# Interface.net
KiCad netlist of a schematic drawn in Altium Designer
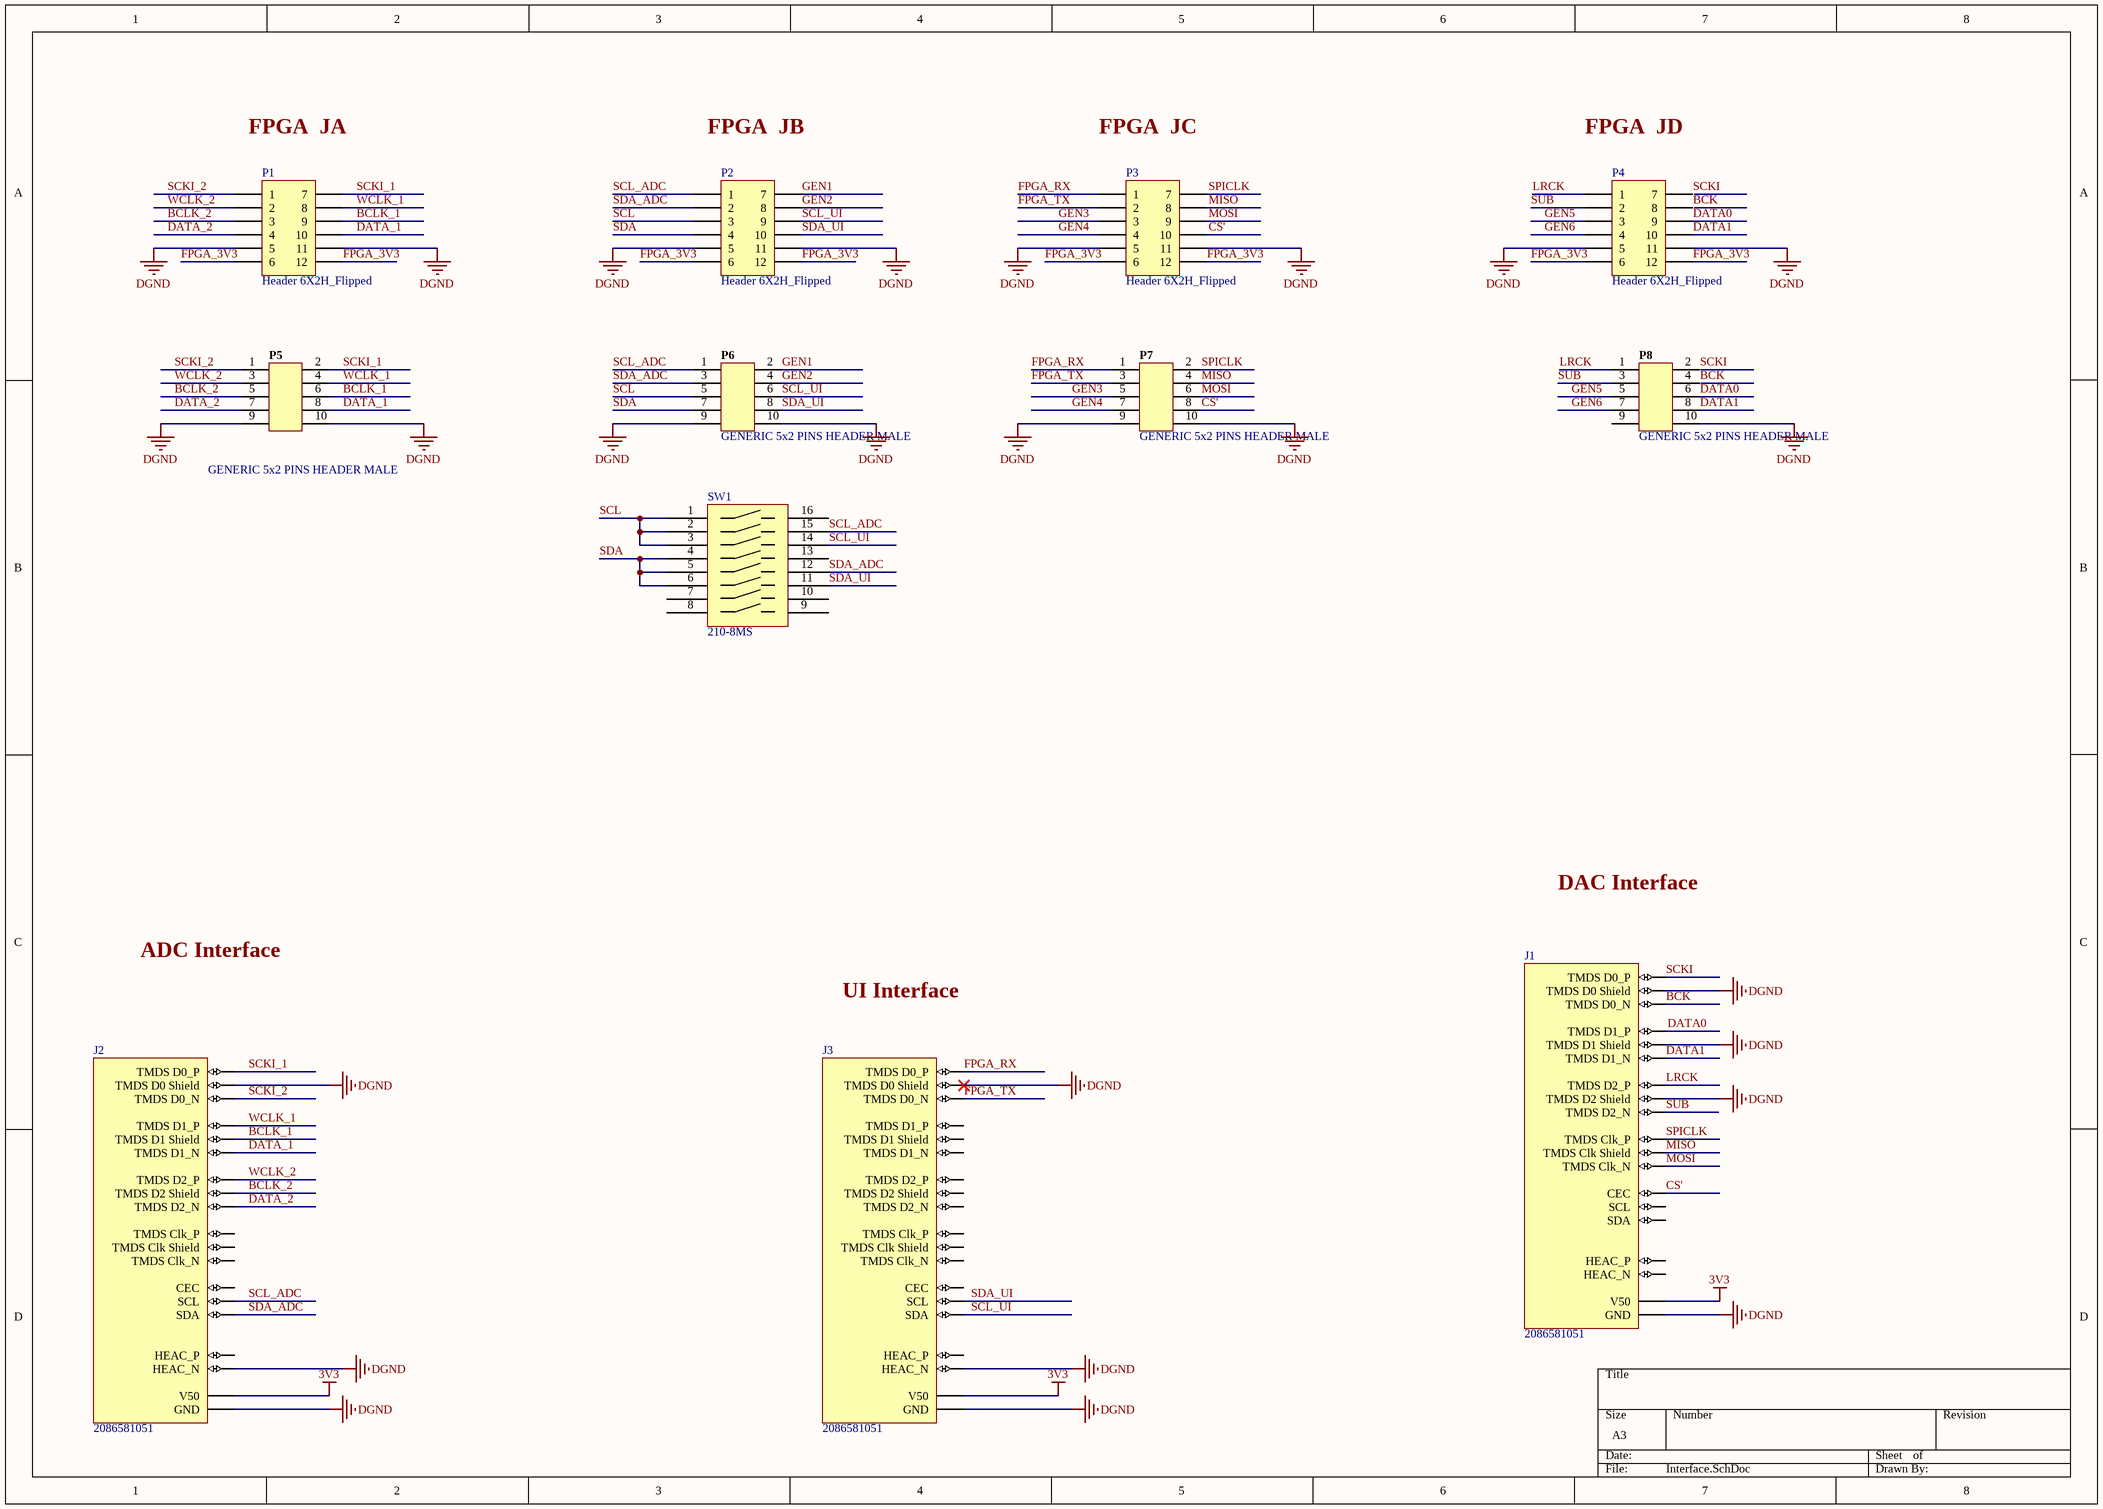
[diagram p0: Interface.SchDoc]

(export (version "E")
  (design (tool "Eeschema 10.0.6"))
  (components
    (comp (ref "J1")
      (value "2086581051")
      (footprint "2086581051")
      (description "CONN FEM SMD 19 90Deg HDMI")
      (fields (field (name "DESIGN ITEM ID") "2086581051") (field (name "MANUFACTURER") "Molex"))
      (libsource (lib "University of Malta - MEMENTO") (part "Symbol"))
    )
    (comp (ref "J2")
      (value "2086581051")
      (footprint "2086581051")
      (description "CONN FEM SMD 19 90Deg HDMI")
      (fields (field (name "DESIGN ITEM ID") "2086581051") (field (name "MANUFACTURER") "Molex"))
      (libsource (lib "University of Malta - MEMENTO") (part "Symbol"))
    )
    (comp (ref "J3")
      (value "2086581051")
      (footprint "2086581051")
      (description "CONN FEM SMD 19 90Deg HDMI")
      (fields (field (name "DESIGN ITEM ID") "2086581051") (field (name "MANUFACTURER") "Molex"))
      (libsource (lib "University of Malta - MEMENTO") (part "Symbol"))
    )
    (comp (ref "P1")
      (value "Header 6X2H_Flipped")
      (footprint "HDR2X6H_Flipped")
      (description "Header, 6-Pin, Dual row, Right Angle, Flipped")
      (fields (field (name "DESIGN ITEM ID") "Header 6X2H_Flipped"))
      (libsource (lib "University of Malta - MEMENTO") (part "Header 6X2H_Flipped"))
    )
    (comp (ref "P2")
      (value "Header 6X2H_Flipped")
      (footprint "HDR2X6H_Flipped")
      (description "Header, 6-Pin, Dual row, Right Angle, Flipped")
      (fields (field (name "DESIGN ITEM ID") "Header 6X2H_Flipped"))
      (libsource (lib "University of Malta - MEMENTO") (part "Header 6X2H_Flipped"))
    )
    (comp (ref "P3")
      (value "Header 6X2H_Flipped")
      (footprint "HDR2X6H_Flipped")
      (description "Header, 6-Pin, Dual row, Right Angle, Flipped")
      (fields (field (name "DESIGN ITEM ID") "Header 6X2H_Flipped"))
      (libsource (lib "University of Malta - MEMENTO") (part "Header 6X2H_Flipped"))
    )
    (comp (ref "P4")
      (value "Header 6X2H_Flipped")
      (footprint "HDR2X6H_Flipped")
      (description "Header, 6-Pin, Dual row, Right Angle, Flipped")
      (fields (field (name "DESIGN ITEM ID") "Header 6X2H_Flipped"))
      (libsource (lib "University of Malta - MEMENTO") (part "Header 6X2H_Flipped"))
    )
    (comp (ref "P5")
      (value "GENERIC 5x2 PINS HEADER MALE")
      (footprint "GENERIC 5PIN 2ROW HEADER 0")
      (description "CONN MAL TH 5x2 0Deg HEADER")
      (fields
        (field (name "DESIGN ITEM ID") "GENERIC 5x2 PINS HEADER MALE")
        (field (name "MANUFACTURER") "Generic")
      )
      (libsource (lib "University of Malta - MEMENTO") (part "GENERIC 5x2 PINS HEADER MALE"))
    )
    (comp (ref "P6")
      (value "GENERIC 5x2 PINS HEADER MALE")
      (footprint "GENERIC 5PIN 2ROW HEADER 0")
      (description "CONN MAL TH 5x2 0Deg HEADER")
      (fields
        (field (name "DESIGN ITEM ID") "GENERIC 5x2 PINS HEADER MALE")
        (field (name "MANUFACTURER") "Generic")
      )
      (libsource (lib "University of Malta - MEMENTO") (part "GENERIC 5x2 PINS HEADER MALE"))
    )
    (comp (ref "P7")
      (value "GENERIC 5x2 PINS HEADER MALE")
      (footprint "GENERIC 5PIN 2ROW HEADER 0")
      (description "CONN MAL TH 5x2 0Deg HEADER")
      (fields
        (field (name "DESIGN ITEM ID") "GENERIC 5x2 PINS HEADER MALE")
        (field (name "MANUFACTURER") "Generic")
      )
      (libsource (lib "University of Malta - MEMENTO") (part "GENERIC 5x2 PINS HEADER MALE"))
    )
    (comp (ref "P8")
      (value "GENERIC 5x2 PINS HEADER MALE")
      (footprint "GENERIC 5PIN 2ROW HEADER 0")
      (description "CONN MAL TH 5x2 0Deg HEADER")
      (fields
        (field (name "DESIGN ITEM ID") "GENERIC 5x2 PINS HEADER MALE")
        (field (name "MANUFACTURER") "Generic")
      )
      (libsource (lib "University of Malta - MEMENTO") (part "GENERIC 5x2 PINS HEADER MALE"))
    )
    (comp (ref "SW1")
      (value "210-8MS")
      (footprint "210-8MS")
      (description "SWITCH DIP SMD SPST 8 100mA 50V")
      (fields (field (name "MANUFACTURER") "C&K Components") (field (name "DESIGN ITEM ID") "210-8MS"))
      (libsource (lib "University of Malta - MEMENTO") (part "210-8MS"))
    )
  )
  (nets
    (net (code "1") (name "/BCK") (class "Default")
      (node (ref "J1") (pin "9") (pinfunction "TMDS_D0_N_9") (pintype "bidirectional"))
      (node (ref "P4") (pin "8") (pinfunction "8_8") (pintype "passive"))
      (node (ref "P8") (pin "4") (pinfunction "4_4") (pintype "passive"))
    )
    (net (code "2") (name "/BCLK_1") (class "Default")
      (node (ref "J2") (pin "5") (pinfunction "TMDS_D1_Shield_5") (pintype "bidirectional"))
      (node (ref "P1") (pin "9") (pinfunction "9_9") (pintype "passive"))
      (node (ref "P5") (pin "6") (pinfunction "6_6") (pintype "passive"))
    )
    (net (code "3") (name "/BCLK_2") (class "Default")
      (node (ref "J2") (pin "2") (pinfunction "TMDS_D2_Shield_2") (pintype "bidirectional"))
      (node (ref "P1") (pin "3") (pinfunction "3_3") (pintype "passive"))
      (node (ref "P5") (pin "5") (pinfunction "5_5") (pintype "passive"))
    )
    (net (code "4") (name "/CS'") (class "Default")
      (node (ref "J1") (pin "13") (pinfunction "CEC_13") (pintype "bidirectional"))
      (node (ref "P3") (pin "10") (pinfunction "10_10") (pintype "passive"))
      (node (ref "P7") (pin "8") (pinfunction "8_8") (pintype "passive"))
    )
    (net (code "5") (name "/DATA0") (class "Default")
      (node (ref "J1") (pin "4") (pinfunction "TMDS_D1_P_4") (pintype "bidirectional"))
      (node (ref "P4") (pin "9") (pinfunction "9_9") (pintype "passive"))
      (node (ref "P8") (pin "6") (pinfunction "6_6") (pintype "passive"))
    )
    (net (code "6") (name "/DATA1") (class "Default")
      (node (ref "J1") (pin "6") (pinfunction "TMDS_D1_N_6") (pintype "bidirectional"))
      (node (ref "P4") (pin "10") (pinfunction "10_10") (pintype "passive"))
      (node (ref "P8") (pin "8") (pinfunction "8_8") (pintype "passive"))
    )
    (net (code "7") (name "/DATA_1") (class "Default")
      (node (ref "J2") (pin "6") (pinfunction "TMDS_D1_N_6") (pintype "bidirectional"))
      (node (ref "P1") (pin "10") (pinfunction "10_10") (pintype "passive"))
      (node (ref "P5") (pin "8") (pinfunction "8_8") (pintype "passive"))
    )
    (net (code "8") (name "/DATA_2") (class "Default")
      (node (ref "J2") (pin "3") (pinfunction "TMDS_D2_N_3") (pintype "bidirectional"))
      (node (ref "P1") (pin "4") (pinfunction "4_4") (pintype "passive"))
      (node (ref "P5") (pin "7") (pinfunction "7_7") (pintype "passive"))
    )
    (net (code "9") (name "/FPGA_3V3") (class "Default")
      (node (ref "P1") (pin "12") (pinfunction "12_12") (pintype "passive"))
      (node (ref "P1") (pin "6") (pinfunction "6_6") (pintype "passive"))
      (node (ref "P2") (pin "12") (pinfunction "12_12") (pintype "passive"))
      (node (ref "P2") (pin "6") (pinfunction "6_6") (pintype "passive"))
      (node (ref "P3") (pin "12") (pinfunction "12_12") (pintype "passive"))
      (node (ref "P3") (pin "6") (pinfunction "6_6") (pintype "passive"))
      (node (ref "P4") (pin "12") (pinfunction "12_12") (pintype "passive"))
      (node (ref "P4") (pin "6") (pinfunction "6_6") (pintype "passive"))
    )
    (net (code "10") (name "/FPGA_RX") (class "Default")
      (node (ref "J3") (pin "7") (pinfunction "TMDS_D0_P_7") (pintype "bidirectional"))
      (node (ref "P3") (pin "1") (pinfunction "1_1") (pintype "passive"))
      (node (ref "P7") (pin "1") (pinfunction "1_1") (pintype "passive"))
    )
    (net (code "11") (name "/FPGA_TX") (class "Default")
      (node (ref "J3") (pin "9") (pinfunction "TMDS_D0_N_9") (pintype "bidirectional"))
      (node (ref "P3") (pin "2") (pinfunction "2_2") (pintype "passive"))
      (node (ref "P7") (pin "3") (pinfunction "3_3") (pintype "passive"))
    )
    (net (code "12") (name "/GEN1") (class "Default")
      (node (ref "P2") (pin "7") (pinfunction "7_7") (pintype "passive"))
      (node (ref "P6") (pin "2") (pinfunction "2_2") (pintype "passive"))
    )
    (net (code "13") (name "/GEN2") (class "Default")
      (node (ref "P2") (pin "8") (pinfunction "8_8") (pintype "passive"))
      (node (ref "P6") (pin "4") (pinfunction "4_4") (pintype "passive"))
    )
    (net (code "14") (name "/GEN3") (class "Default")
      (node (ref "P3") (pin "3") (pinfunction "3_3") (pintype "passive"))
      (node (ref "P7") (pin "5") (pinfunction "5_5") (pintype "passive"))
    )
    (net (code "15") (name "/GEN4") (class "Default")
      (node (ref "P3") (pin "4") (pinfunction "4_4") (pintype "passive"))
      (node (ref "P7") (pin "7") (pinfunction "7_7") (pintype "passive"))
    )
    (net (code "16") (name "/GEN5") (class "Default")
      (node (ref "P4") (pin "3") (pinfunction "3_3") (pintype "passive"))
      (node (ref "P8") (pin "5") (pinfunction "5_5") (pintype "passive"))
    )
    (net (code "17") (name "/GEN6") (class "Default")
      (node (ref "P4") (pin "4") (pinfunction "4_4") (pintype "passive"))
      (node (ref "P8") (pin "7") (pinfunction "7_7") (pintype "passive"))
    )
    (net (code "18") (name "/LRCK") (class "Default")
      (node (ref "J1") (pin "1") (pinfunction "TMDS_D2_P_1") (pintype "bidirectional"))
      (node (ref "P4") (pin "1") (pinfunction "1_1") (pintype "passive"))
      (node (ref "P8") (pin "1") (pinfunction "1_1") (pintype "passive"))
    )
    (net (code "19") (name "/MISO") (class "Default")
      (node (ref "J1") (pin "11") (pinfunction "TMDS_Clk_Shield_11") (pintype "bidirectional"))
      (node (ref "P3") (pin "8") (pinfunction "8_8") (pintype "passive"))
      (node (ref "P7") (pin "4") (pinfunction "4_4") (pintype "passive"))
    )
    (net (code "20") (name "/MOSI") (class "Default")
      (node (ref "J1") (pin "12") (pinfunction "TMDS_Clk_N_12") (pintype "bidirectional"))
      (node (ref "P3") (pin "9") (pinfunction "9_9") (pintype "passive"))
      (node (ref "P7") (pin "6") (pinfunction "6_6") (pintype "passive"))
    )
    (net (code "21") (name "/SCKI") (class "Default")
      (node (ref "J1") (pin "7") (pinfunction "TMDS_D0_P_7") (pintype "bidirectional"))
      (node (ref "P4") (pin "7") (pinfunction "7_7") (pintype "passive"))
      (node (ref "P8") (pin "2") (pinfunction "2_2") (pintype "passive"))
    )
    (net (code "22") (name "/SCKI_1") (class "Default")
      (node (ref "J2") (pin "7") (pinfunction "TMDS_D0_P_7") (pintype "bidirectional"))
      (node (ref "P1") (pin "7") (pinfunction "7_7") (pintype "passive"))
      (node (ref "P5") (pin "2") (pinfunction "2_2") (pintype "passive"))
    )
    (net (code "23") (name "/SCKI_2") (class "Default")
      (node (ref "J2") (pin "9") (pinfunction "TMDS_D0_N_9") (pintype "bidirectional"))
      (node (ref "P1") (pin "1") (pinfunction "1_1") (pintype "passive"))
      (node (ref "P5") (pin "1") (pinfunction "1_1") (pintype "passive"))
    )
    (net (code "24") (name "/SCL") (class "Default")
      (node (ref "P2") (pin "3") (pinfunction "3_3") (pintype "passive"))
      (node (ref "P6") (pin "5") (pinfunction "5_5") (pintype "passive"))
      (node (ref "SW1") (pin "1") (pinfunction "SW1_1") (pintype "passive"))
      (node (ref "SW1") (pin "2") (pinfunction "SW2_2") (pintype "passive"))
      (node (ref "SW1") (pin "3") (pinfunction "SW3_3") (pintype "passive"))
    )
    (net (code "25") (name "/SCL_ADC") (class "Default")
      (node (ref "J2") (pin "15") (pinfunction "SCL_15") (pintype "bidirectional"))
      (node (ref "P2") (pin "1") (pinfunction "1_1") (pintype "passive"))
      (node (ref "P6") (pin "1") (pinfunction "1_1") (pintype "passive"))
      (node (ref "SW1") (pin "15") (pinfunction "SW2.in_15") (pintype "passive"))
    )
    (net (code "26") (name "/SCL_UI") (class "Default")
      (node (ref "J3") (pin "16") (pinfunction "SDA_16") (pintype "bidirectional"))
      (node (ref "P2") (pin "9") (pinfunction "9_9") (pintype "passive"))
      (node (ref "P6") (pin "6") (pinfunction "6_6") (pintype "passive"))
      (node (ref "SW1") (pin "14") (pinfunction "SW3.in_14") (pintype "passive"))
    )
    (net (code "27") (name "/SDA") (class "Default")
      (node (ref "P2") (pin "4") (pinfunction "4_4") (pintype "passive"))
      (node (ref "P6") (pin "7") (pinfunction "7_7") (pintype "passive"))
      (node (ref "SW1") (pin "4") (pinfunction "SW4_4") (pintype "passive"))
      (node (ref "SW1") (pin "5") (pinfunction "SW1_5") (pintype "passive"))
      (node (ref "SW1") (pin "6") (pinfunction "SW2_6") (pintype "passive"))
    )
    (net (code "28") (name "/SDA_ADC") (class "Default")
      (node (ref "J2") (pin "16") (pinfunction "SDA_16") (pintype "bidirectional"))
      (node (ref "P2") (pin "2") (pinfunction "2_2") (pintype "passive"))
      (node (ref "P6") (pin "3") (pinfunction "3_3") (pintype "passive"))
      (node (ref "SW1") (pin "12") (pinfunction "SW1.in_12") (pintype "passive"))
    )
    (net (code "29") (name "/SDA_UI") (class "Default")
      (node (ref "J3") (pin "15") (pinfunction "SCL_15") (pintype "bidirectional"))
      (node (ref "P2") (pin "10") (pinfunction "10_10") (pintype "passive"))
      (node (ref "P6") (pin "8") (pinfunction "8_8") (pintype "passive"))
      (node (ref "SW1") (pin "11") (pinfunction "SW2.in_11") (pintype "passive"))
    )
    (net (code "30") (name "/SPICLK") (class "Default")
      (node (ref "J1") (pin "10") (pinfunction "TMDS_Clk_P_10") (pintype "bidirectional"))
      (node (ref "P3") (pin "7") (pinfunction "7_7") (pintype "passive"))
      (node (ref "P7") (pin "2") (pinfunction "2_2") (pintype "passive"))
    )
    (net (code "31") (name "/SUB") (class "Default")
      (node (ref "J1") (pin "3") (pinfunction "TMDS_D2_N_3") (pintype "bidirectional"))
      (node (ref "P4") (pin "2") (pinfunction "2_2") (pintype "passive"))
      (node (ref "P8") (pin "3") (pinfunction "3_3") (pintype "passive"))
    )
    (net (code "32") (name "/WCLK_1") (class "Default")
      (node (ref "J2") (pin "4") (pinfunction "TMDS_D1_P_4") (pintype "bidirectional"))
      (node (ref "P1") (pin "8") (pinfunction "8_8") (pintype "passive"))
      (node (ref "P5") (pin "4") (pinfunction "4_4") (pintype "passive"))
    )
    (net (code "33") (name "/WCLK_2") (class "Default")
      (node (ref "J2") (pin "1") (pinfunction "TMDS_D2_P_1") (pintype "bidirectional"))
      (node (ref "P1") (pin "2") (pinfunction "2_2") (pintype "passive"))
      (node (ref "P5") (pin "3") (pinfunction "3_3") (pintype "passive"))
    )
    (net (code "34") (name "3V3") (class "Default")
      (node (ref "J1") (pin "18") (pinfunction "V50_18") (pintype "power_in"))
      (node (ref "J2") (pin "18") (pinfunction "V50_18") (pintype "power_in"))
      (node (ref "J3") (pin "18") (pinfunction "V50_18") (pintype "power_in"))
    )
    (net (code "35") (name "DGND") (class "Default")
      (node (ref "J1") (pin "17") (pinfunction "GND_17") (pintype "power_in"))
      (node (ref "J1") (pin "2") (pinfunction "TMDS_D2_Shield_2") (pintype "bidirectional"))
      (node (ref "J1") (pin "5") (pinfunction "TMDS_D1_Shield_5") (pintype "bidirectional"))
      (node (ref "J1") (pin "8") (pinfunction "TMDS_D0_Shield_8") (pintype "bidirectional"))
      (node (ref "J2") (pin "17") (pinfunction "GND_17") (pintype "power_in"))
      (node (ref "J2") (pin "19") (pinfunction "HEAC_N_19") (pintype "bidirectional"))
      (node (ref "J2") (pin "8") (pinfunction "TMDS_D0_Shield_8") (pintype "bidirectional"))
      (node (ref "J3") (pin "17") (pinfunction "GND_17") (pintype "power_in"))
      (node (ref "J3") (pin "19") (pinfunction "HEAC_N_19") (pintype "bidirectional"))
      (node (ref "J3") (pin "8") (pinfunction "TMDS_D0_Shield_8") (pintype "bidirectional"))
      (node (ref "P1") (pin "11") (pinfunction "11_11") (pintype "passive"))
      (node (ref "P1") (pin "5") (pinfunction "5_5") (pintype "passive"))
      (node (ref "P2") (pin "11") (pinfunction "11_11") (pintype "passive"))
      (node (ref "P2") (pin "5") (pinfunction "5_5") (pintype "passive"))
      (node (ref "P3") (pin "11") (pinfunction "11_11") (pintype "passive"))
      (node (ref "P3") (pin "5") (pinfunction "5_5") (pintype "passive"))
      (node (ref "P4") (pin "11") (pinfunction "11_11") (pintype "passive"))
      (node (ref "P4") (pin "5") (pinfunction "5_5") (pintype "passive"))
      (node (ref "P5") (pin "10") (pinfunction "10_10") (pintype "passive"))
      (node (ref "P5") (pin "9") (pinfunction "9_9") (pintype "passive"))
      (node (ref "P6") (pin "10") (pinfunction "10_10") (pintype "passive"))
      (node (ref "P6") (pin "9") (pinfunction "9_9") (pintype "passive"))
      (node (ref "P7") (pin "10") (pinfunction "10_10") (pintype "passive"))
      (node (ref "P7") (pin "9") (pinfunction "9_9") (pintype "passive"))
      (node (ref "P8") (pin "10") (pinfunction "10_10") (pintype "passive"))
    )
    (net (code "36") (name "unconnected-(J1-HEAC_N-Pad19)") (class "Default")
      (node (ref "J1") (pin "19") (pinfunction "HEAC_N_19") (pintype "bidirectional"))
    )
    (net (code "37") (name "unconnected-(J1-HEAC_P-Pad14)") (class "Default")
      (node (ref "J1") (pin "14") (pinfunction "HEAC_P_14") (pintype "bidirectional"))
    )
    (net (code "38") (name "unconnected-(J1-SCL-Pad15)") (class "Default")
      (node (ref "J1") (pin "15") (pinfunction "SCL_15") (pintype "bidirectional"))
    )
    (net (code "39") (name "unconnected-(J1-SDA-Pad16)") (class "Default")
      (node (ref "J1") (pin "16") (pinfunction "SDA_16") (pintype "bidirectional"))
    )
    (net (code "40") (name "unconnected-(J2-CEC-Pad13)") (class "Default")
      (node (ref "J2") (pin "13") (pinfunction "CEC_13") (pintype "bidirectional"))
    )
    (net (code "41") (name "unconnected-(J2-HEAC_P-Pad14)") (class "Default")
      (node (ref "J2") (pin "14") (pinfunction "HEAC_P_14") (pintype "bidirectional"))
    )
    (net (code "42") (name "unconnected-(J2-TMDS_Clk_N-Pad12)") (class "Default")
      (node (ref "J2") (pin "12") (pinfunction "TMDS_Clk_N_12") (pintype "bidirectional"))
    )
    (net (code "43") (name "unconnected-(J2-TMDS_Clk_P-Pad10)") (class "Default")
      (node (ref "J2") (pin "10") (pinfunction "TMDS_Clk_P_10") (pintype "bidirectional"))
    )
    (net (code "44") (name "unconnected-(J2-TMDS_Clk_Shield-Pad11)") (class "Default")
      (node (ref "J2") (pin "11") (pinfunction "TMDS_Clk_Shield_11") (pintype "bidirectional"))
    )
    (net (code "45") (name "unconnected-(J3-CEC-Pad13)") (class "Default")
      (node (ref "J3") (pin "13") (pinfunction "CEC_13") (pintype "bidirectional"))
    )
    (net (code "46") (name "unconnected-(J3-HEAC_P-Pad14)") (class "Default")
      (node (ref "J3") (pin "14") (pinfunction "HEAC_P_14") (pintype "bidirectional"))
    )
    (net (code "47") (name "unconnected-(J3-TMDS_Clk_N-Pad12)") (class "Default")
      (node (ref "J3") (pin "12") (pinfunction "TMDS_Clk_N_12") (pintype "bidirectional"))
    )
    (net (code "48") (name "unconnected-(J3-TMDS_Clk_P-Pad10)") (class "Default")
      (node (ref "J3") (pin "10") (pinfunction "TMDS_Clk_P_10") (pintype "bidirectional"))
    )
    (net (code "49") (name "unconnected-(J3-TMDS_Clk_Shield-Pad11)") (class "Default")
      (node (ref "J3") (pin "11") (pinfunction "TMDS_Clk_Shield_11") (pintype "bidirectional"))
    )
    (net (code "50") (name "unconnected-(J3-TMDS_D1_N-Pad6)") (class "Default")
      (node (ref "J3") (pin "6") (pinfunction "TMDS_D1_N_6") (pintype "bidirectional"))
    )
    (net (code "51") (name "unconnected-(J3-TMDS_D1_P-Pad4)") (class "Default")
      (node (ref "J3") (pin "4") (pinfunction "TMDS_D1_P_4") (pintype "bidirectional"))
    )
    (net (code "52") (name "unconnected-(J3-TMDS_D1_Shield-Pad5)") (class "Default")
      (node (ref "J3") (pin "5") (pinfunction "TMDS_D1_Shield_5") (pintype "bidirectional"))
    )
    (net (code "53") (name "unconnected-(J3-TMDS_D2_N-Pad3)") (class "Default")
      (node (ref "J3") (pin "3") (pinfunction "TMDS_D2_N_3") (pintype "bidirectional"))
    )
    (net (code "54") (name "unconnected-(J3-TMDS_D2_P-Pad1)") (class "Default")
      (node (ref "J3") (pin "1") (pinfunction "TMDS_D2_P_1") (pintype "bidirectional"))
    )
    (net (code "55") (name "unconnected-(J3-TMDS_D2_Shield-Pad2)") (class "Default")
      (node (ref "J3") (pin "2") (pinfunction "TMDS_D2_Shield_2") (pintype "bidirectional"))
    )
    (net (code "56") (name "unconnected-(P8-Pad9)") (class "Default")
      (node (ref "P8") (pin "9") (pinfunction "9_9") (pintype "passive"))
    )
    (net (code "57") (name "unconnected-(SW1-Pad7)") (class "Default")
      (node (ref "SW1") (pin "7") (pinfunction "7_7") (pintype "passive"))
    )
    (net (code "58") (name "unconnected-(SW1-SW1-Pad16)") (class "Default")
      (node (ref "SW1") (pin "16") (pinfunction "SW1_16") (pintype "passive"))
    )
    (net (code "59") (name "unconnected-(SW1-SW3.in-Pad10)") (class "Default")
      (node (ref "SW1") (pin "10") (pinfunction "SW3.in_10") (pintype "passive"))
    )
    (net (code "60") (name "unconnected-(SW1-SW4-Pad8)") (class "Default")
      (node (ref "SW1") (pin "8") (pinfunction "SW4_8") (pintype "passive"))
    )
    (net (code "61") (name "unconnected-(SW1-SW4.in-Pad9)") (class "Default")
      (node (ref "SW1") (pin "9") (pinfunction "SW4.in_9") (pintype "passive"))
    )
    (net (code "62") (name "unconnected-(SW1-SW4.in-Pad13)") (class "Default")
      (node (ref "SW1") (pin "13") (pinfunction "SW4.in_13") (pintype "passive"))
    )
  )
)
